# scheme.net
KiCad netlist of a schematic drawn in EAGLE
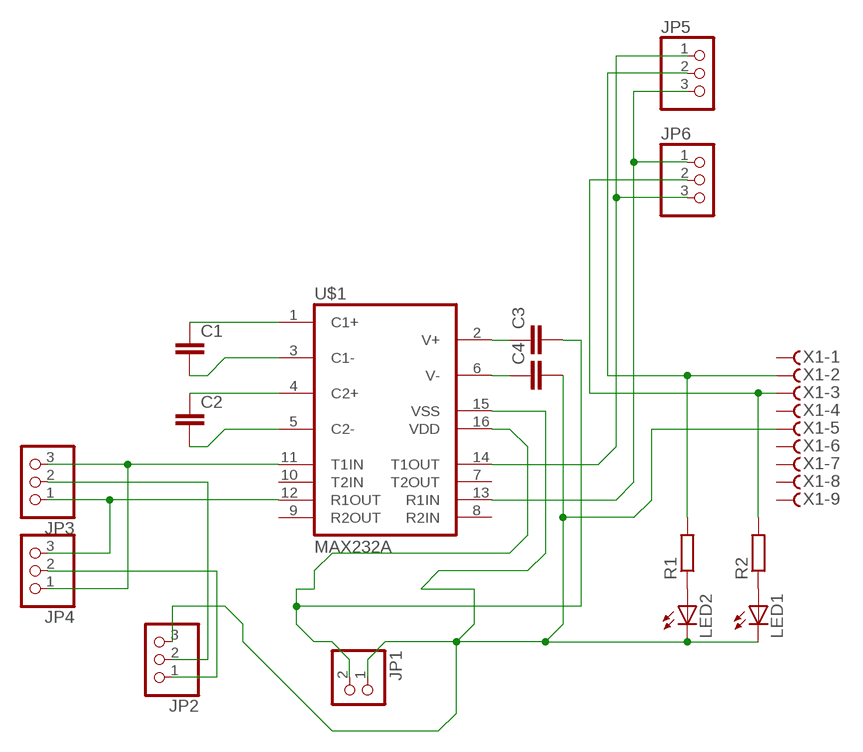
[diagram p0: schematic, sheet 1]

(export (version "E")
  (design (tool "Eeschema 10.0.6"))
  (components
    (comp (ref "C1")
      (value "C-EUC1206")
      (footprint "eagle-import:C1206")
      (libsource (lib "eagle-import") (part "C-EUC1206"))
    )
    (comp (ref "C2")
      (value "C-EUC1206")
      (footprint "eagle-import:C1206")
      (libsource (lib "eagle-import") (part "C-EUC1206"))
    )
    (comp (ref "C3")
      (value "C-EUC1206")
      (footprint "eagle-import:C1206")
      (libsource (lib "eagle-import") (part "C-EUC1206"))
    )
    (comp (ref "C4")
      (value "C-EUC1206")
      (footprint "eagle-import:C1206")
      (libsource (lib "eagle-import") (part "C-EUC1206"))
    )
    (comp (ref "JP1")
      (value "PINHD-1X2")
      (footprint "eagle-import:1X02")
      (libsource (lib "eagle-import") (part "PINHD-1X2"))
    )
    (comp (ref "JP2")
      (value "PINHD-1X3")
      (footprint "eagle-import:1X03")
      (libsource (lib "eagle-import") (part "pinhead_PINHD-1X3"))
    )
    (comp (ref "JP3")
      (value "PINHD-1X3")
      (footprint "eagle-import:1X03")
      (libsource (lib "eagle-import") (part "PINHD-1X3"))
    )
    (comp (ref "JP4")
      (value "PINHD-1X3")
      (footprint "eagle-import:1X03")
      (libsource (lib "eagle-import") (part "PINHD-1X3"))
    )
    (comp (ref "JP5")
      (value "PINHD-1X3")
      (footprint "eagle-import:1X03")
      (libsource (lib "eagle-import") (part "PINHD-1X3"))
    )
    (comp (ref "JP6")
      (value "PINHD-1X3")
      (footprint "eagle-import:1X03")
      (libsource (lib "eagle-import") (part "PINHD-1X3"))
    )
    (comp (ref "LED1")
      (value "LED3MM")
      (footprint "eagle-import:LED3MM")
      (libsource (lib "eagle-import") (part "LED3MM"))
    )
    (comp (ref "LED2")
      (value "LED3MM")
      (footprint "eagle-import:LED3MM")
      (libsource (lib "eagle-import") (part "LED3MM"))
    )
    (comp (ref "R1")
      (value "R-EU_R1206")
      (footprint "eagle-import:R1206")
      (libsource (lib "eagle-import") (part "R-EU_R1206"))
    )
    (comp (ref "R2")
      (value "R-EU_R1206")
      (footprint "eagle-import:R1206")
      (libsource (lib "eagle-import") (part "R-EU_R1206"))
    )
    (comp (ref "U$1")
      (value "MAX232A")
      (footprint "eagle-import:SO16")
      (libsource (lib "eagle-import") (part "MAX232A"))
    )
    (comp (ref "X1")
      (value "F09HS")
      (footprint "eagle-import:F09H")
      (libsource (lib "eagle-import") (part "F09?SH"))
    )
  )
  (nets
    (net (code "1") (name "Net-(JP2-Pad1)") (class "Default")
      (node (ref "JP2") (pin "1") (pinfunction "1_1") (pintype "passive"))
      (node (ref "JP4") (pin "2") (pinfunction "2_2") (pintype "passive"))
    )
    (net (code "2") (name "Net-(JP2-Pad2)") (class "Default")
      (node (ref "JP2") (pin "2") (pinfunction "2_2") (pintype "passive"))
      (node (ref "JP3") (pin "2") (pinfunction "2_2") (pintype "passive"))
    )
    (net (code "3") (name "Net-(LED1-C)") (class "Default")
      (node (ref "C4") (pin "2") (pinfunction "2_2") (pintype "passive"))
      (node (ref "JP1") (pin "1") (pinfunction "1_1") (pintype "passive"))
      (node (ref "JP2") (pin "3") (pinfunction "3_3") (pintype "passive"))
      (node (ref "LED1") (pin "K") (pinfunction "C_K") (pintype "passive"))
      (node (ref "LED2") (pin "K") (pinfunction "C_K") (pintype "passive"))
      (node (ref "U$1") (pin "15") (pinfunction "VSS_15") (pintype "bidirectional"))
      (node (ref "X1") (pin "5") (pinfunction "F_5") (pintype "passive"))
    )
    (net (code "4") (name "Net-(LED1-PadA)") (class "Default")
      (node (ref "LED1") (pin "A") (pinfunction "A_A") (pintype "passive"))
      (node (ref "R2") (pin "1") (pinfunction "1_1") (pintype "passive"))
    )
    (net (code "5") (name "Net-(LED2-PadA)") (class "Default")
      (node (ref "LED2") (pin "A") (pinfunction "A_A") (pintype "passive"))
      (node (ref "R1") (pin "1") (pinfunction "1_1") (pintype "passive"))
    )
    (net (code "6") (name "Net-(U$1-C1+)") (class "Default")
      (node (ref "C1") (pin "1") (pinfunction "1_1") (pintype "passive"))
      (node (ref "U$1") (pin "1") (pinfunction "C1+_1") (pintype "bidirectional"))
    )
    (net (code "7") (name "Net-(U$1-C1-)") (class "Default")
      (node (ref "C1") (pin "2") (pinfunction "2_2") (pintype "passive"))
      (node (ref "U$1") (pin "3") (pinfunction "C1-_3") (pintype "bidirectional"))
    )
    (net (code "8") (name "Net-(U$1-C2+)") (class "Default")
      (node (ref "C2") (pin "1") (pinfunction "1_1") (pintype "passive"))
      (node (ref "U$1") (pin "4") (pinfunction "C2+_4") (pintype "bidirectional"))
    )
    (net (code "9") (name "Net-(U$1-C2-)") (class "Default")
      (node (ref "C2") (pin "2") (pinfunction "2_2") (pintype "passive"))
      (node (ref "U$1") (pin "5") (pinfunction "C2-_5") (pintype "bidirectional"))
    )
    (net (code "10") (name "Net-(U$1-R1IN)") (class "Default")
      (node (ref "JP5") (pin "3") (pinfunction "3_3") (pintype "passive"))
      (node (ref "JP6") (pin "1") (pinfunction "1_1") (pintype "passive"))
      (node (ref "U$1") (pin "13") (pinfunction "R1IN_13") (pintype "input"))
    )
    (net (code "11") (name "Net-(U$1-R1OUT)") (class "Default")
      (node (ref "JP3") (pin "1") (pinfunction "1_1") (pintype "passive"))
      (node (ref "JP4") (pin "3") (pinfunction "3_3") (pintype "passive"))
      (node (ref "U$1") (pin "12") (pinfunction "R1OUT_12") (pintype "output"))
    )
    (net (code "12") (name "Net-(U$1-T1IN)") (class "Default")
      (node (ref "JP3") (pin "3") (pinfunction "3_3") (pintype "passive"))
      (node (ref "JP4") (pin "1") (pinfunction "1_1") (pintype "passive"))
      (node (ref "U$1") (pin "11") (pinfunction "T1IN_11") (pintype "input"))
    )
    (net (code "13") (name "Net-(U$1-T1OUT)") (class "Default")
      (node (ref "JP5") (pin "1") (pinfunction "1_1") (pintype "passive"))
      (node (ref "JP6") (pin "3") (pinfunction "3_3") (pintype "passive"))
      (node (ref "U$1") (pin "14") (pinfunction "T1OUT_14") (pintype "output"))
    )
    (net (code "14") (name "Net-(U$1-V+)") (class "Default")
      (node (ref "C3") (pin "1") (pinfunction "1_1") (pintype "passive"))
      (node (ref "U$1") (pin "2") (pinfunction "V+_2") (pintype "bidirectional"))
    )
    (net (code "15") (name "Net-(U$1-V-)") (class "Default")
      (node (ref "C4") (pin "1") (pinfunction "1_1") (pintype "passive"))
      (node (ref "U$1") (pin "6") (pinfunction "V-_6") (pintype "bidirectional"))
    )
    (net (code "16") (name "Net-(U$1-VDD)") (class "Default")
      (node (ref "C3") (pin "2") (pinfunction "2_2") (pintype "passive"))
      (node (ref "JP1") (pin "2") (pinfunction "2_2") (pintype "passive"))
      (node (ref "U$1") (pin "16") (pinfunction "VDD_16") (pintype "bidirectional"))
    )
    (net (code "17") (name "Net-(X1B-F)") (class "Default")
      (node (ref "JP5") (pin "2") (pinfunction "2_2") (pintype "passive"))
      (node (ref "R1") (pin "2") (pinfunction "2_2") (pintype "passive"))
      (node (ref "X1") (pin "2") (pinfunction "F_2") (pintype "passive"))
    )
    (net (code "18") (name "Net-(X1C-F)") (class "Default")
      (node (ref "JP6") (pin "2") (pinfunction "2_2") (pintype "passive"))
      (node (ref "R2") (pin "2") (pinfunction "2_2") (pintype "passive"))
      (node (ref "X1") (pin "3") (pinfunction "F_3") (pintype "passive"))
    )
    (net (code "19") (name "unconnected-(U$1-R2IN-Pad8)") (class "Default")
      (node (ref "U$1") (pin "8") (pinfunction "R2IN_8") (pintype "input"))
    )
    (net (code "20") (name "unconnected-(U$1-R2OUT-Pad9)") (class "Default")
      (node (ref "U$1") (pin "9") (pinfunction "R2OUT_9") (pintype "output"))
    )
    (net (code "21") (name "unconnected-(U$1-T2IN-Pad10)") (class "Default")
      (node (ref "U$1") (pin "10") (pinfunction "T2IN_10") (pintype "input"))
    )
    (net (code "22") (name "unconnected-(U$1-T2OUT-Pad7)") (class "Default")
      (node (ref "U$1") (pin "7") (pinfunction "T2OUT_7") (pintype "output"))
    )
    (net (code "23") (name "unconnected-(X1A-F-Pad1)") (class "Default")
      (node (ref "X1") (pin "1") (pinfunction "F_1") (pintype "passive"))
    )
    (net (code "24") (name "unconnected-(X1D-F-Pad4)") (class "Default")
      (node (ref "X1") (pin "4") (pinfunction "F_4") (pintype "passive"))
    )
    (net (code "25") (name "unconnected-(X1F-F-Pad6)") (class "Default")
      (node (ref "X1") (pin "6") (pinfunction "F_6") (pintype "passive"))
    )
    (net (code "26") (name "unconnected-(X1G-F-Pad7)") (class "Default")
      (node (ref "X1") (pin "7") (pinfunction "F_7") (pintype "passive"))
    )
    (net (code "27") (name "unconnected-(X1H-F-Pad8)") (class "Default")
      (node (ref "X1") (pin "8") (pinfunction "F_8") (pintype "passive"))
    )
    (net (code "28") (name "unconnected-(X1I-F-Pad9)") (class "Default")
      (node (ref "X1") (pin "9") (pinfunction "F_9") (pintype "passive"))
    )
  )
)
